# SCH_hacker-card_2025-04-14.net
KiCad netlist of a schematic drawn in EasyEDA
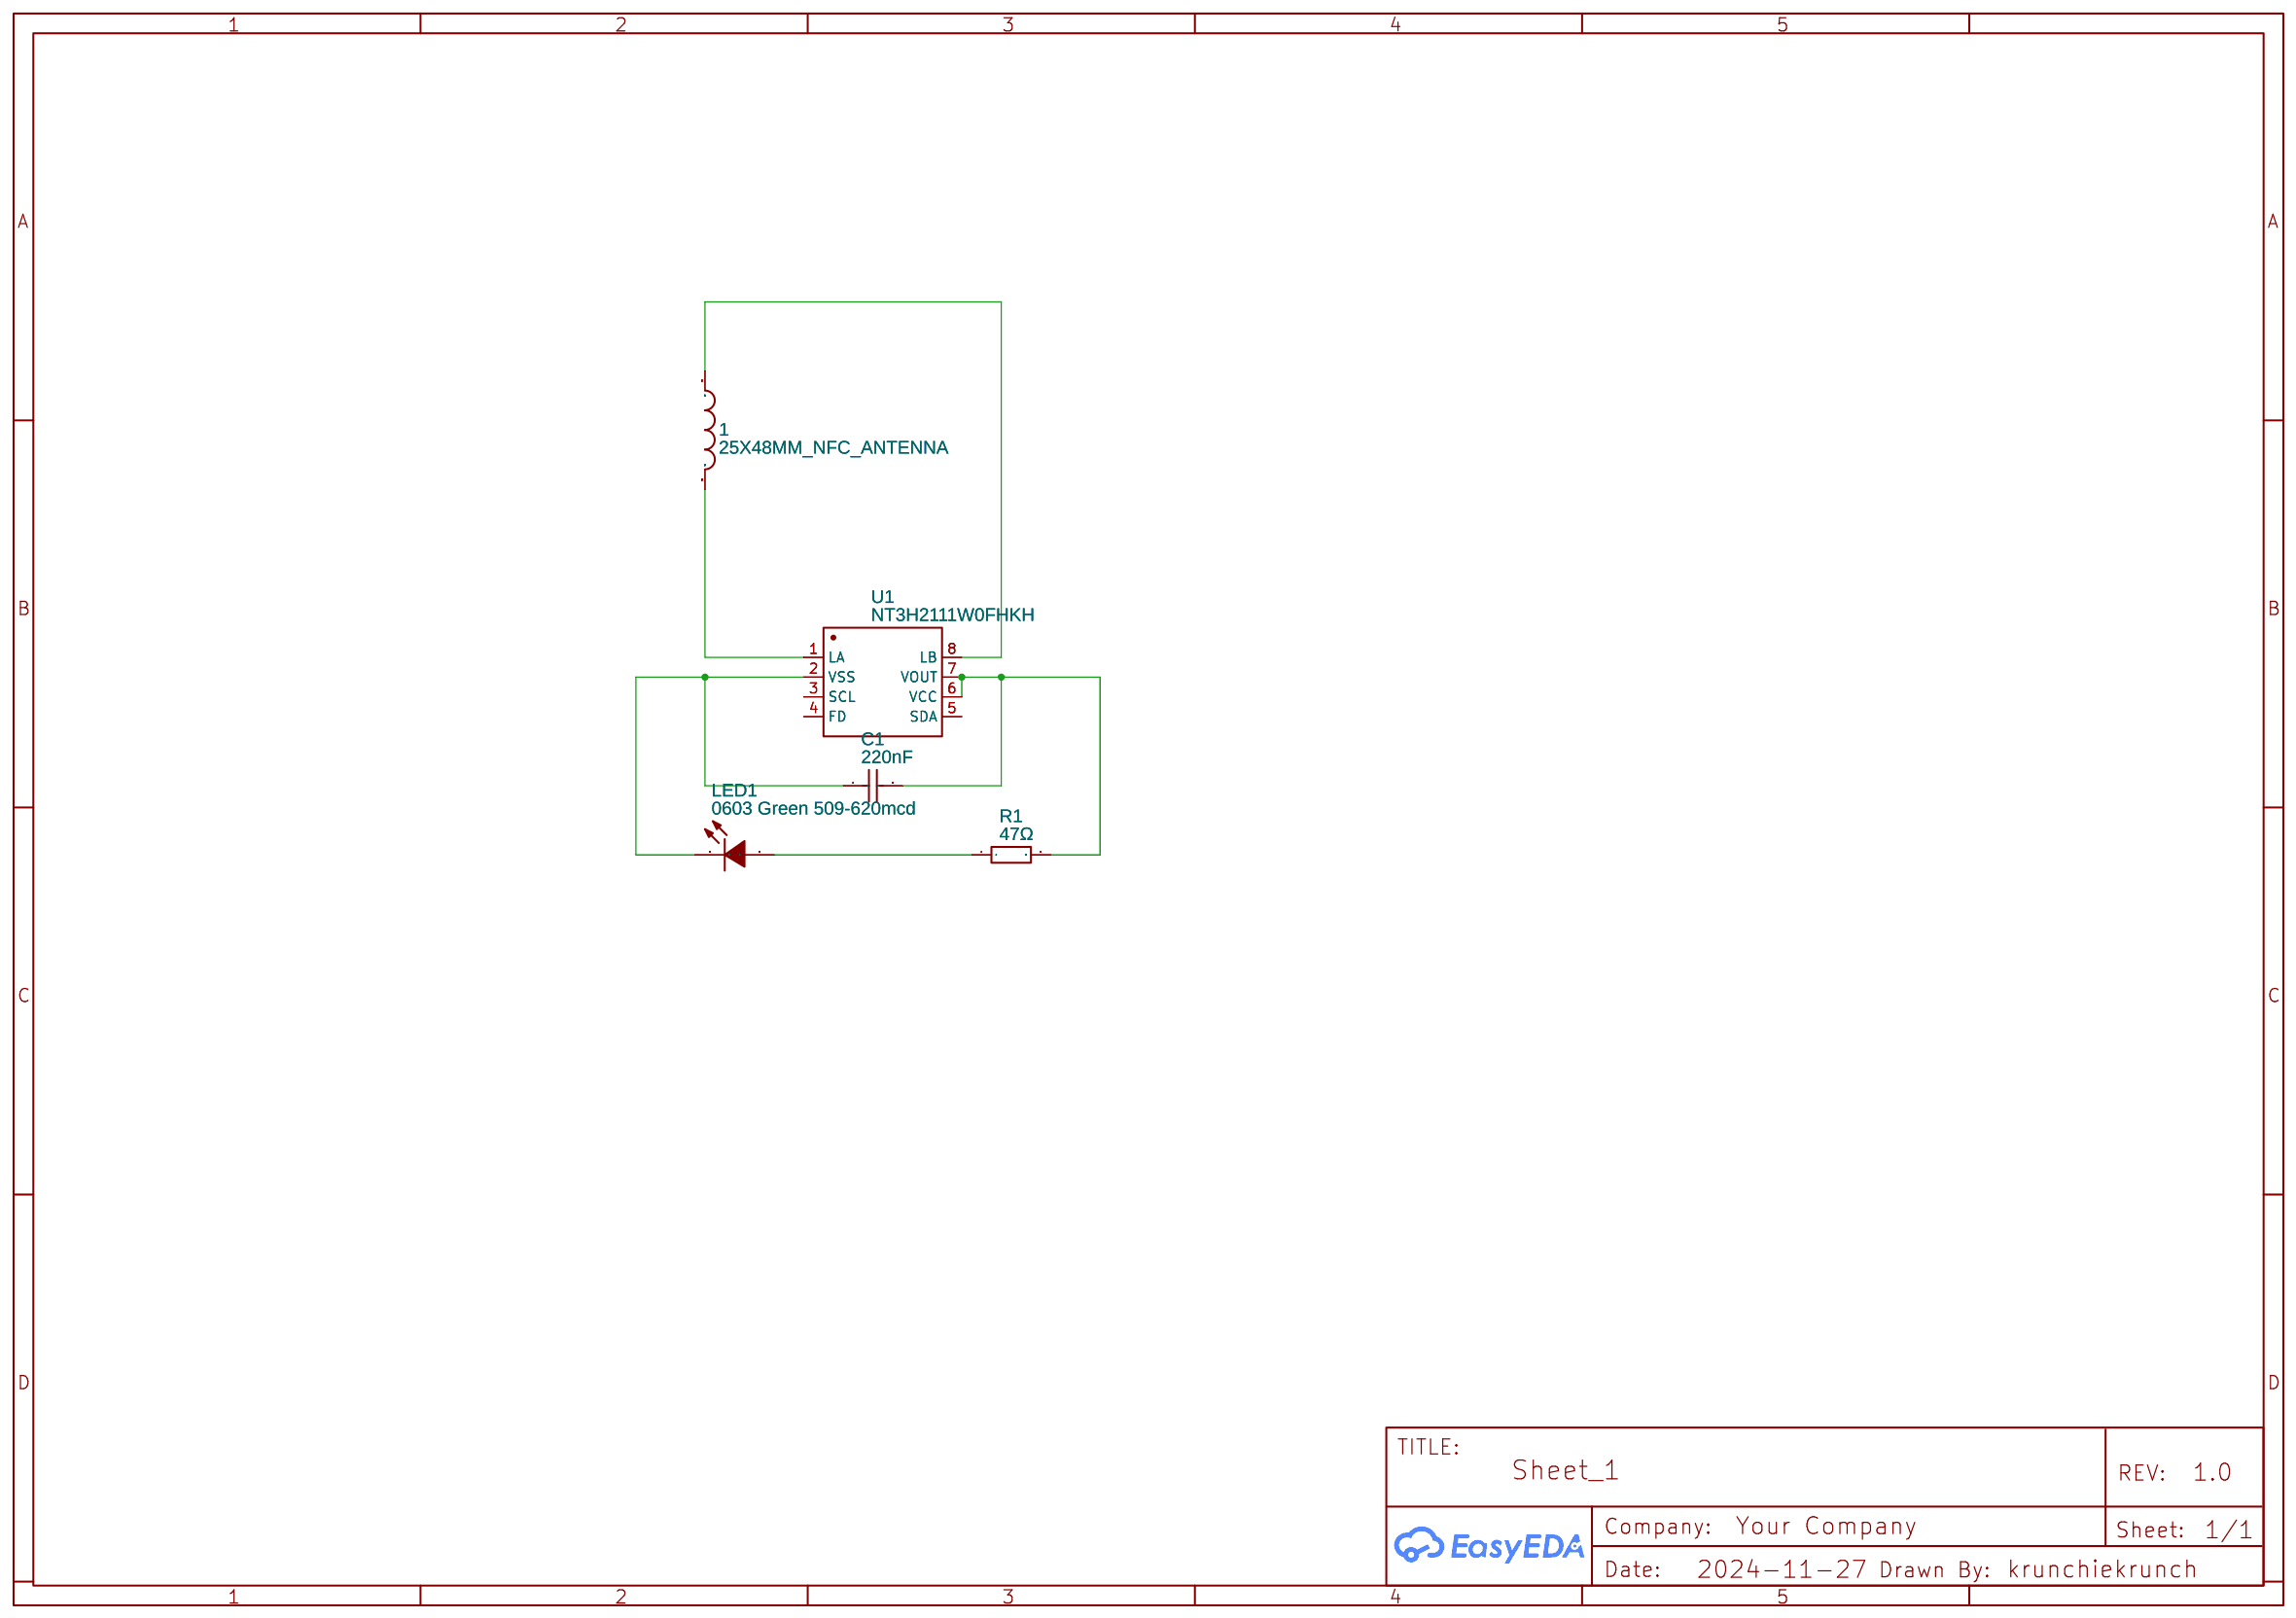
[diagram p0: schematic sheet]

(export (version "E")
  (design (tool "Eeschema 10.0.6"))
  (components
    (comp (ref "1") (value "25X48MM_NFC_ANTENNA") (libsource (lib "") (part "25X48MM_NFC_ANTENNA")))
    (comp (ref "C1")
      (value "220nF")
      (fields
        (field (name "Manufacturer Part") "CL10B224KA8NNNC")
        (field (name "Manufacturer") "SAMSUNG(三星)")
      )
      (libsource (lib "") (part "CL10B224KA8NNNC"))
    )
    (comp (ref "LED1")
      (value "0603 Green 509-620mcd")
      (fields (field (name "Manufacturer Part") "KT-0603G") (field (name "Manufacturer") "KENTO"))
      (libsource (lib "") (part "0603 Green 509-620mcd"))
    )
    (comp (ref "R1")
      (value "47Ω")
      (fields
        (field (name "Manufacturer Part") "0603WAF470JT5E")
        (field (name "Manufacturer") "UNI-ROYAL(厚声)")
      )
      (libsource (lib "") (part "0603WAF470JT5E"))
    )
    (comp (ref "U1")
      (value "NT3H2111W0FHKH")
      (fields (field (name "Manufacturer") "NXP(恩智浦)"))
      (libsource (lib "") (part "NT3H2111W0FHKH"))
    )
  )
  (nets
    (net (code "1") (name "Net-(LED1-A)") (class "Default")
      (node (ref "LED1") (pin "2") (pinfunction "A_2") (pintype "unspecified"))
      (node (ref "R1") (pin "1") (pinfunction "1_1") (pintype "input"))
    )
    (net (code "2") (name "Net-(LED1-K)") (class "Default")
      (node (ref "C1") (pin "1") (pinfunction "1_1") (pintype "input"))
      (node (ref "LED1") (pin "1") (pinfunction "K_1") (pintype "unspecified"))
      (node (ref "U1") (pin "2") (pinfunction "VSS_2") (pintype "unspecified"))
    )
    (net (code "3") (name "Net-(U1-LA)") (class "Default")
      (node (ref "1") (pin "P$2") (pinfunction "P$2_P$2") (pintype "bidirectional"))
      (node (ref "U1") (pin "1") (pinfunction "LA_1") (pintype "unspecified"))
    )
    (net (code "4") (name "Net-(U1-LB)") (class "Default")
      (node (ref "1") (pin "P$1") (pinfunction "P$1_P$1") (pintype "bidirectional"))
      (node (ref "U1") (pin "8") (pinfunction "LB_8") (pintype "unspecified"))
    )
    (net (code "5") (name "Net-(U1-VCC)") (class "Default")
      (node (ref "C1") (pin "2") (pinfunction "2_2") (pintype "input"))
      (node (ref "R1") (pin "2") (pinfunction "2_2") (pintype "input"))
      (node (ref "U1") (pin "6") (pinfunction "VCC_6") (pintype "unspecified"))
      (node (ref "U1") (pin "7") (pinfunction "VOUT_7") (pintype "unspecified"))
    )
    (net (code "6") (name "unconnected-(U1-FD-Pad4)") (class "Default")
      (node (ref "U1") (pin "4") (pinfunction "FD_4") (pintype "unspecified"))
    )
    (net (code "7") (name "unconnected-(U1-SCL-Pad3)") (class "Default")
      (node (ref "U1") (pin "3") (pinfunction "SCL_3") (pintype "unspecified"))
    )
    (net (code "8") (name "unconnected-(U1-SDA-Pad5)") (class "Default")
      (node (ref "U1") (pin "5") (pinfunction "SDA_5") (pintype "unspecified"))
    )
  )
)
